# 02_ldo1v8.net
KiCad netlist of a schematic drawn in Altium Designer
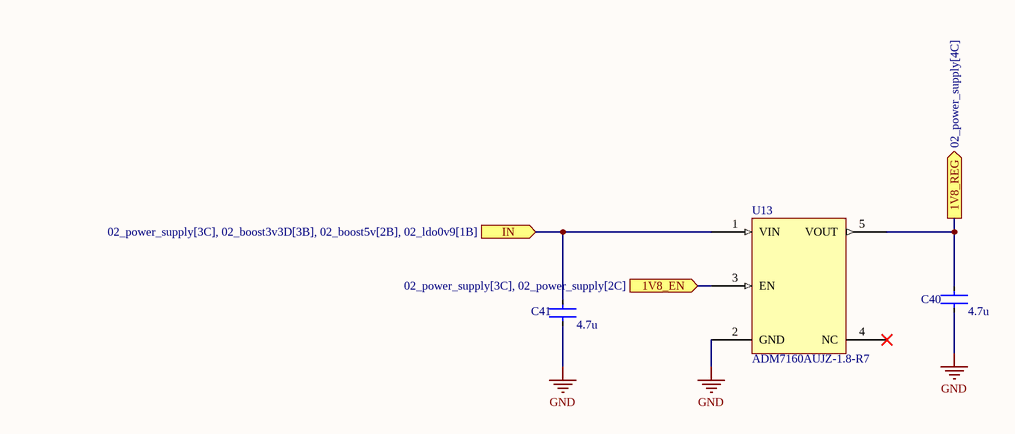
[diagram p0: 02_ldo1v8.SchDoc]

(export (version "E")
  (design (tool "Eeschema 10.0.6"))
  (components
    (comp (ref "C40")
      (value "C1608X5R1E475K080AC")
      (footprint "CAPTDK0603")
      (description "CAP CER 4.7UF 25V X5R 0603")
      (libsource (lib "tcspc00") (part "C1608X5R1E475K080AC"))
    )
    (comp (ref "C41")
      (value "C1608X5R1E475K080AC")
      (footprint "CAPTDK0603")
      (description "CAP CER 4.7UF 25V X5R 0603")
      (libsource (lib "tcspc00") (part "C1608X5R1E475K080AC"))
    )
    (comp (ref "U13")
      (value "ADM7160AUJZ-1.8-R7")
      (footprint "ADM7160")
      (description "IC REG LINEAR 1.8V 200MA TSOT5")
      (fields (field (name "MANUFACTURER") "Analog Devices"))
      (libsource (lib "tcspc00") (part "ADM7160AUJZ-1.8-R7"))
    )
  )
  (nets
    (net (code "1") (name "/1V8_EN") (class "Default")
      (node (ref "U13") (pin "3") (pinfunction "EN_3") (pintype "input"))
    )
    (net (code "2") (name "/1V8_REG") (class "Default")
      (node (ref "C40") (pin "1") (pinfunction "1_1") (pintype "passive"))
      (node (ref "U13") (pin "5") (pinfunction "VOUT_5") (pintype "output"))
    )
    (net (code "3") (name "/IN") (class "Default")
      (node (ref "C41") (pin "1") (pinfunction "1_1") (pintype "passive"))
      (node (ref "U13") (pin "1") (pinfunction "VIN_1") (pintype "input"))
    )
    (net (code "4") (name "GND") (class "Default")
      (node (ref "C40") (pin "2") (pinfunction "2_2") (pintype "passive"))
      (node (ref "C41") (pin "2") (pinfunction "2_2") (pintype "passive"))
      (node (ref "U13") (pin "2") (pinfunction "GND_2") (pintype "power_in"))
    )
    (net (code "5") (name "unconnected-(U13-NC-Pad4)") (class "Default")
      (node (ref "U13") (pin "4") (pinfunction "NC_4") (pintype "passive+no_connect"))
    )
  )
)
